# Reader_PN5108.net
KiCad netlist of a schematic drawn in Altium Designer
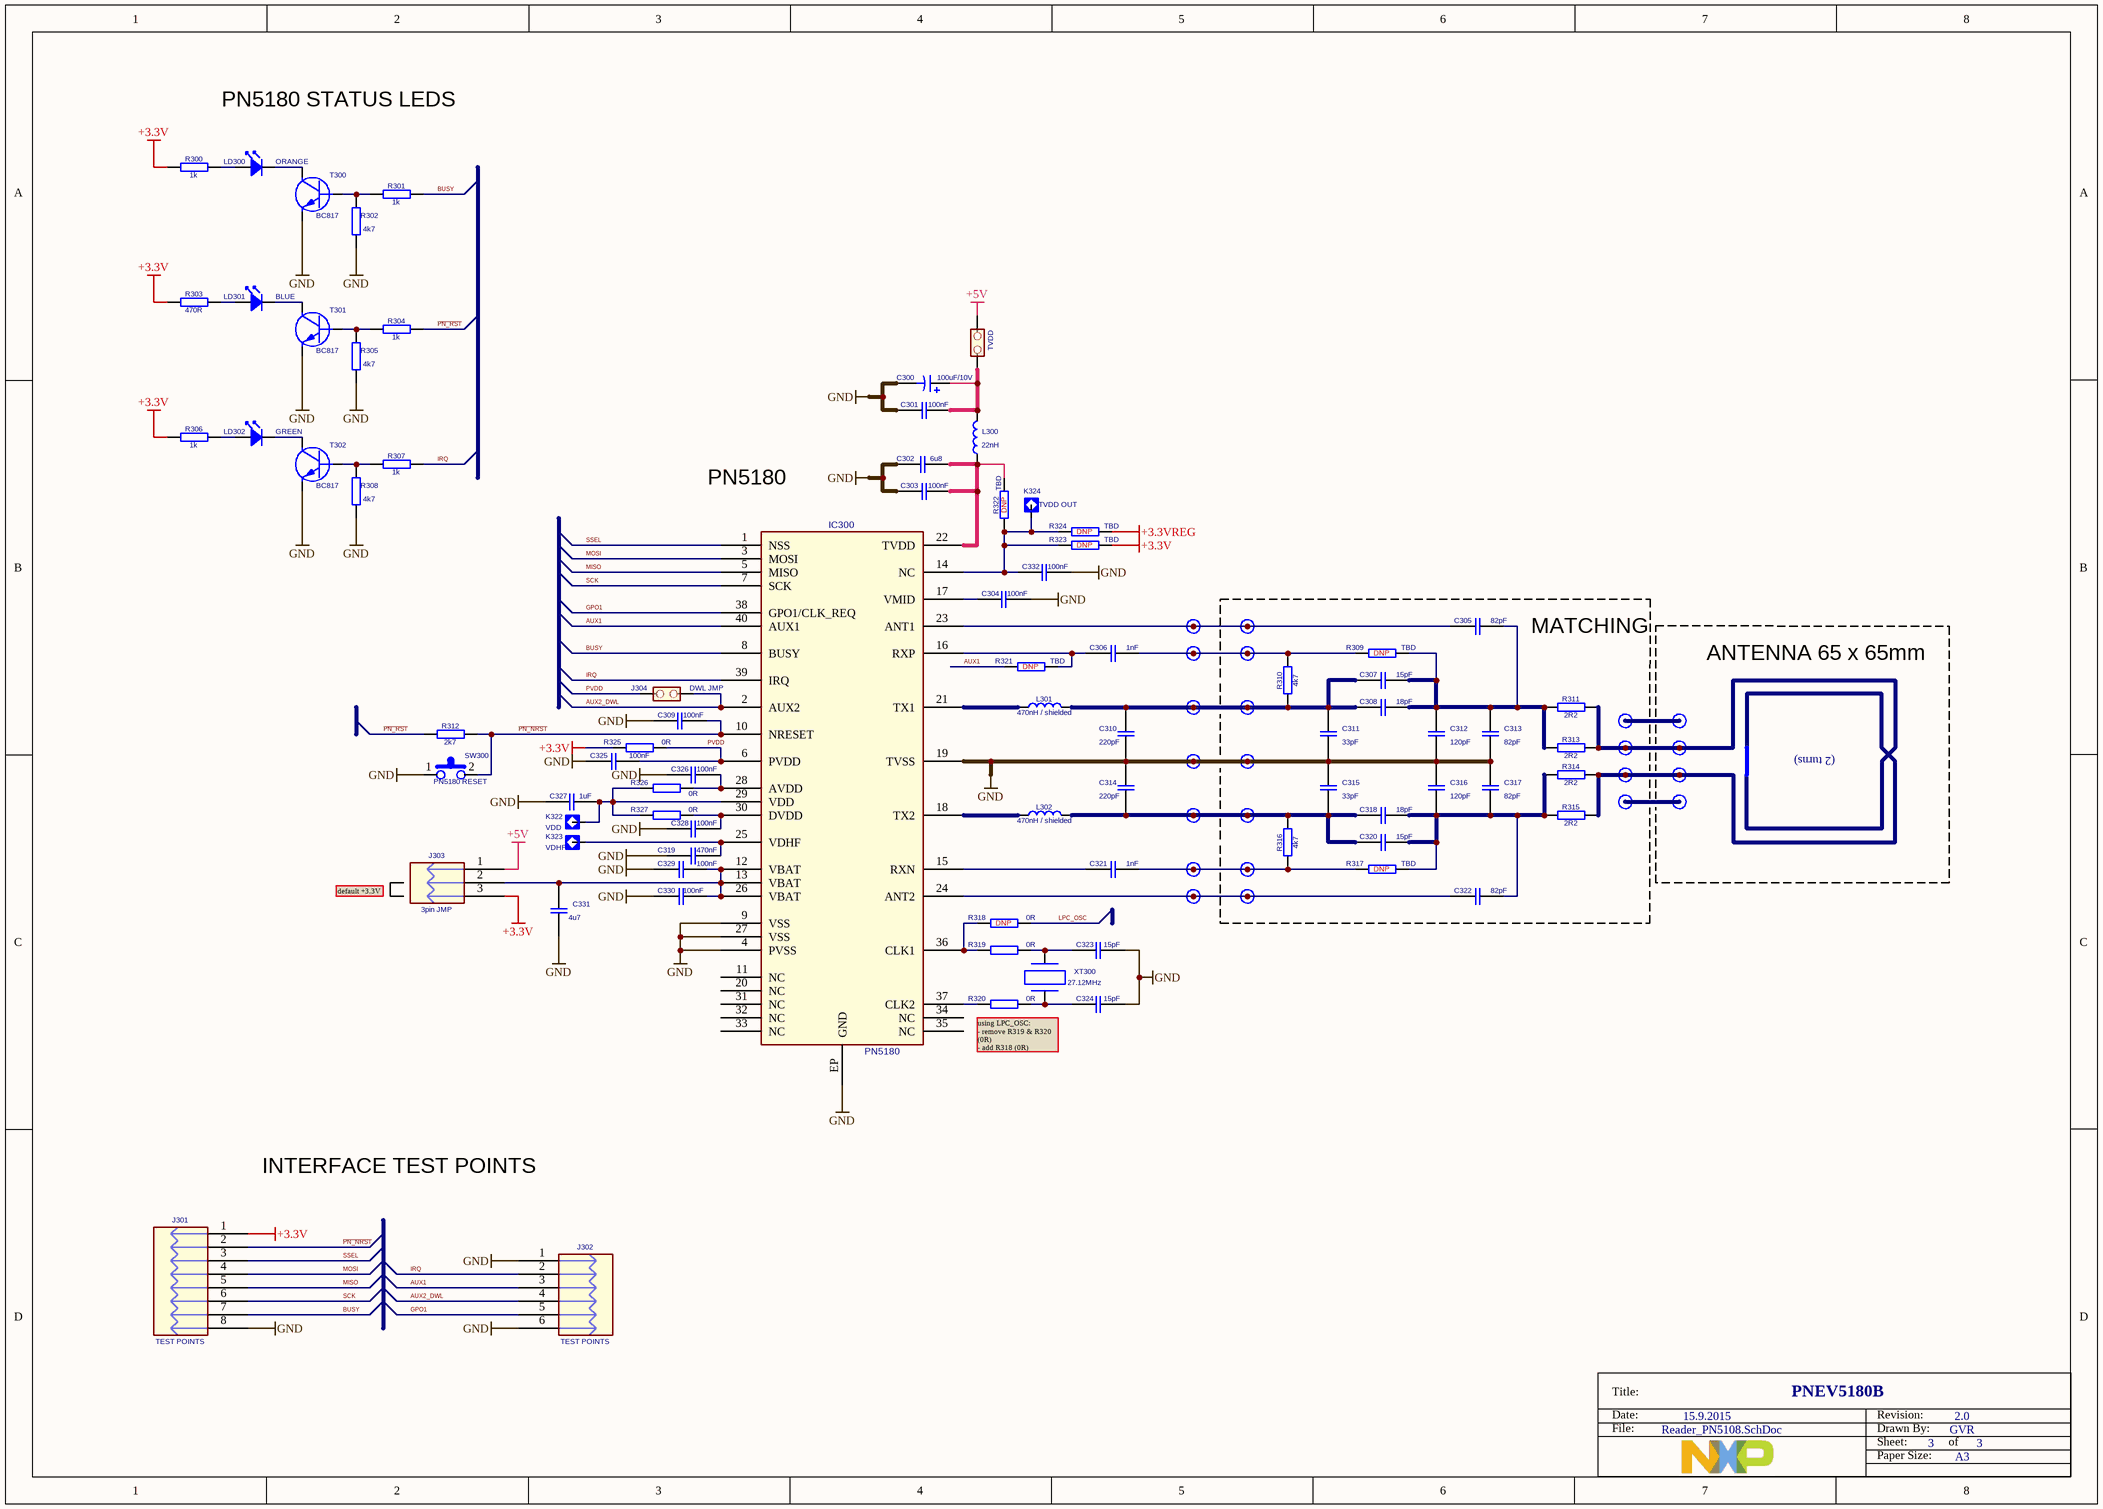
[diagram p0: Reader_PN5108.SchDoc]

(export (version "E")
  (design (tool "Eeschema 10.0.6"))
  (components
    (comp (ref "C300")
      (value "100uF/10V")
      (footprint "ALT_CP:C_TANTAL_B")
      (description "C_TANTAL_B")
      (libsource (lib "ALT_CP") (part "C_TANTAL_B"))
    )
    (comp (ref "C301")
      (value "100nF")
      (footprint "Y0603")
      (description "CAPC0603")
      (libsource (lib "ALT_CP") (part "CAPC0603"))
    )
    (comp (ref "C302")
      (value "6u8")
      (footprint "Y0603")
      (description "CAPC0603")
      (libsource (lib "ALT_CP") (part "CAPC0603"))
    )
    (comp (ref "C303")
      (value "100nF")
      (footprint "Y0603")
      (description "CAPC0603")
      (libsource (lib "ALT_CP") (part "CAPC0603"))
    )
    (comp (ref "C304")
      (value "100nF")
      (footprint "Y0603")
      (description "CAPC0603")
      (libsource (lib "ALT_CP") (part "CAPC0603"))
    )
    (comp (ref "C305")
      (value "82pF")
      (footprint "Y0805")
      (description "CAPC0805")
      (libsource (lib "ALT_CP") (part "CAPC0805"))
    )
    (comp (ref "C306")
      (value "1nF")
      (footprint "Y0805")
      (description "CAPC0805")
      (libsource (lib "ALT_CP") (part "CAPC0805"))
    )
    (comp (ref "C307")
      (value "15pF")
      (footprint "Y0805")
      (description "CAPC0805")
      (libsource (lib "ALT_CP") (part "CAPC0805"))
    )
    (comp (ref "C308")
      (value "18pF")
      (footprint "Y0805")
      (description "CAPC0805")
      (libsource (lib "ALT_CP") (part "CAPC0805"))
    )
    (comp (ref "C309")
      (value "100nF")
      (footprint "Y0603")
      (description "CAPC0603")
      (libsource (lib "ALT_CP") (part "CAPC0603"))
    )
    (comp (ref "C310")
      (value "220pF")
      (footprint "Y0805")
      (description "CAPC0805")
      (libsource (lib "ALT_CP") (part "CAPC0805"))
    )
    (comp (ref "C311")
      (value "33pF")
      (footprint "Y0805")
      (description "CAPC0805")
      (libsource (lib "ALT_CP") (part "CAPC0805"))
    )
    (comp (ref "C312")
      (value "120pF")
      (footprint "Y0805")
      (description "CAPC0805")
      (libsource (lib "ALT_CP") (part "CAPC0805"))
    )
    (comp (ref "C313")
      (value "82pF")
      (footprint "Y0805")
      (description "CAPC0805")
      (libsource (lib "ALT_CP") (part "CAPC0805"))
    )
    (comp (ref "C314")
      (value "220pF")
      (footprint "Y0805")
      (description "CAPC0805")
      (libsource (lib "ALT_CP") (part "CAPC0805"))
    )
    (comp (ref "C315")
      (value "33pF")
      (footprint "Y0805")
      (description "CAPC0805")
      (libsource (lib "ALT_CP") (part "CAPC0805"))
    )
    (comp (ref "C316")
      (value "120pF")
      (footprint "Y0805")
      (description "CAPC0805")
      (libsource (lib "ALT_CP") (part "CAPC0805"))
    )
    (comp (ref "C317")
      (value "82pF")
      (footprint "Y0805")
      (description "CAPC0805")
      (libsource (lib "ALT_CP") (part "CAPC0805"))
    )
    (comp (ref "C318")
      (value "18pF")
      (footprint "Y0805")
      (description "CAPC0805")
      (libsource (lib "ALT_CP") (part "CAPC0805"))
    )
    (comp (ref "C319")
      (value "470nF")
      (footprint "Y0603")
      (description "CAPC0603")
      (libsource (lib "ALT_CP") (part "CAPC0603"))
    )
    (comp (ref "C320")
      (value "15pF")
      (footprint "Y0805")
      (description "CAPC0805")
      (libsource (lib "ALT_CP") (part "CAPC0805"))
    )
    (comp (ref "C321")
      (value "1nF")
      (footprint "Y0805")
      (description "CAPC0805")
      (libsource (lib "ALT_CP") (part "CAPC0805"))
    )
    (comp (ref "C322")
      (value "82pF")
      (footprint "Y0805")
      (description "CAPC0805")
      (libsource (lib "ALT_CP") (part "CAPC0805"))
    )
    (comp (ref "C323")
      (value "15pF")
      (footprint "Y0603")
      (description "CAPC0603")
      (libsource (lib "ALT_CP") (part "CAPC0603"))
    )
    (comp (ref "C324")
      (value "15pF")
      (footprint "Y0603")
      (description "CAPC0603")
      (libsource (lib "ALT_CP") (part "CAPC0603"))
    )
    (comp (ref "C325")
      (value "100nF")
      (footprint "ALT_CP:Y0402")
      (description "CAPC0402")
      (libsource (lib "ALT_CP") (part "CAPC0402"))
    )
    (comp (ref "C326")
      (value "100nF")
      (footprint "Y0603")
      (description "CAPC0603")
      (libsource (lib "ALT_CP") (part "CAPC0603"))
    )
    (comp (ref "C327")
      (value "1uF")
      (footprint "Y0603")
      (description "CAPC0603")
      (libsource (lib "ALT_CP") (part "CAPC0603"))
    )
    (comp (ref "C328")
      (value "100nF")
      (footprint "Y0603")
      (description "CAPC0603")
      (libsource (lib "ALT_CP") (part "CAPC0603"))
    )
    (comp (ref "C329")
      (value "100nF")
      (footprint "ALT_CP:Y0402")
      (description "CAPC0402")
      (libsource (lib "ALT_CP") (part "CAPC0402"))
    )
    (comp (ref "C330")
      (value "100nF")
      (footprint "ALT_CP:Y0402")
      (description "CAPC0402")
      (libsource (lib "ALT_CP") (part "CAPC0402"))
    )
    (comp (ref "C331")
      (value "4u7")
      (footprint "Y0603")
      (description "CAPC0603")
      (libsource (lib "ALT_CP") (part "CAPC0603"))
    )
    (comp (ref "C332")
      (value "100nF")
      (footprint "Y0603")
      (description "CAPC0603")
      (libsource (lib "ALT_CP") (part "CAPC0603"))
    )
    (comp (ref "IC300")
      (value "PN5180")
      (footprint "ALT_CP:QFN50P600X600X100_HS-41N")
      (description "13.56 MHz Reader")
      (libsource (lib "ALT_CP") (part "PN5180"))
    )
    (comp (ref "J300")
      (value "TVDD")
      (footprint "CON2")
      (description "JMP2")
      (libsource (lib "") (part "JMP2_1"))
    )
    (comp (ref "J301")
      (value "TEST POINTS")
      (footprint "ALT_CP:CON8M-LINE")
      (description "CON8M_LINE")
      (libsource (lib "ALT_CP") (part "CON8M_LINE"))
    )
    (comp (ref "J302")
      (value "TEST POINTS")
      (footprint "ALT_CP:CON6M-LINE")
      (description "CON6M_LINE")
      (libsource (lib "ALT_CP") (part "CON6M_LINE"))
    )
    (comp (ref "J303")
      (value "3pin JMP")
      (footprint "ALT_CP:CON3M-LINE")
      (description "CON3M_LINE")
      (libsource (lib "ALT_CP") (part "CON3M_LINE"))
    )
    (comp (ref "J304")
      (value "DWL JMP")
      (footprint "CON2")
      (description "JMP2")
      (libsource (lib "ALT_CP") (part "JMP2"))
    )
    (comp (ref "K300")
      (value "TP_1.0mm")
      (footprint "CON1_PIN_Round_1.0x1.8mm")
      (libsource (lib "ALT_CP") (part "TP_1.0mm"))
    )
    (comp (ref "K301")
      (value "TP_1.0mm")
      (footprint "CON1_PIN_Round_1.0x1.8mm")
      (libsource (lib "ALT_CP") (part "TP_1.0mm"))
    )
    (comp (ref "K302")
      (value "TP_1.0mm")
      (footprint "CON1_PIN_Round_1.0x1.8mm")
      (libsource (lib "ALT_CP") (part "TP_1.0mm"))
    )
    (comp (ref "K303")
      (value "TP_1.0mm")
      (footprint "CON1_PIN_Round_1.0x1.8mm")
      (libsource (lib "ALT_CP") (part "TP_1.0mm"))
    )
    (comp (ref "K304")
      (value "TP_1.0mm")
      (footprint "CON1_PIN_Round_1.0x1.8mm")
      (libsource (lib "ALT_CP") (part "TP_1.0mm"))
    )
    (comp (ref "K305")
      (value "TP_1.0mm")
      (footprint "CON1_PIN_Round_1.0x1.8mm")
      (libsource (lib "ALT_CP") (part "TP_1.0mm"))
    )
    (comp (ref "K306")
      (value "TP_1.0mm")
      (footprint "CON1_PIN_Round_1.0x1.8mm")
      (libsource (lib "ALT_CP") (part "TP_1.0mm"))
    )
    (comp (ref "K307")
      (value "TP_1.0mm")
      (footprint "CON1_PIN_Round_1.0x1.8mm")
      (libsource (lib "ALT_CP") (part "TP_1.0mm"))
    )
    (comp (ref "K308")
      (value "TP_1.0mm")
      (footprint "CON1_PIN_Round_1.0x1.8mm")
      (libsource (lib "ALT_CP") (part "TP_1.0mm"))
    )
    (comp (ref "K309")
      (value "TP_1.0mm")
      (footprint "CON1_PIN_Round_1.0x1.8mm")
      (libsource (lib "ALT_CP") (part "TP_1.0mm"))
    )
    (comp (ref "K310")
      (value "TP_1.0mm")
      (footprint "CON1_PIN_Round_1.0x1.8mm")
      (libsource (lib "ALT_CP") (part "TP_1.0mm"))
    )
    (comp (ref "K311")
      (value "TP_1.0mm")
      (footprint "CON1_PIN_Round_1.0x1.8mm")
      (libsource (lib "ALT_CP") (part "TP_1.0mm"))
    )
    (comp (ref "K312")
      (value "TP_1.0mm")
      (footprint "CON1_PIN_Round_1.0x1.8mm")
      (libsource (lib "ALT_CP") (part "TP_1.0mm"))
    )
    (comp (ref "K313")
      (value "TP_1.0mm")
      (footprint "CON1_PIN_Round_1.0x1.8mm")
      (libsource (lib "ALT_CP") (part "TP_1.0mm"))
    )
    (comp (ref "K314")
      (value "TP_1.0mm")
      (footprint "CON1_PIN_Round_1.0x1.8mm")
      (libsource (lib "ALT_CP") (part "TP_1.0mm"))
    )
    (comp (ref "K315")
      (value "TP_1.0mm")
      (footprint "CON1_PIN_Round_1.0x1.8mm")
      (libsource (lib "ALT_CP") (part "TP_1.0mm"))
    )
    (comp (ref "K316")
      (value "TP_1.0mm")
      (footprint "CON1_PIN_Round_1.0x1.8mm")
      (libsource (lib "ALT_CP") (part "TP_1.0mm"))
    )
    (comp (ref "K317")
      (value "TP_1.0mm")
      (footprint "CON1_PIN_Round_1.0x1.8mm")
      (libsource (lib "ALT_CP") (part "TP_1.0mm"))
    )
    (comp (ref "K318")
      (value "TP_1.0mm")
      (footprint "CON1_PIN_Round_1.0x1.8mm")
      (libsource (lib "ALT_CP") (part "TP_1.0mm"))
    )
    (comp (ref "K319")
      (value "TP_1.0mm")
      (footprint "CON1_PIN_Round_1.0x1.8mm")
      (libsource (lib "ALT_CP") (part "TP_1.0mm"))
    )
    (comp (ref "K320")
      (value "TP_1.0mm")
      (footprint "CON1_PIN_Round_1.0x1.8mm")
      (libsource (lib "ALT_CP") (part "TP_1.0mm"))
    )
    (comp (ref "K321")
      (value "TP_1.0mm")
      (footprint "CON1_PIN_Round_1.0x1.8mm")
      (libsource (lib "ALT_CP") (part "TP_1.0mm"))
    )
    (comp (ref "K322")
      (value "VDD")
      (footprint "ALT_CP:TESTP_ROUND_1.0mm")
      (description "TP1")
      (libsource (lib "ALT_CP") (part "TP1"))
    )
    (comp (ref "K323")
      (value "VDHF")
      (footprint "ALT_CP:TESTP_ROUND_1.0mm")
      (description "TP1")
      (libsource (lib "ALT_CP") (part "TP1"))
    )
    (comp (ref "K324")
      (value "TVDD OUT")
      (footprint "ALT_CP:TESTP_ROUND_1.0mm")
      (description "TP1")
      (libsource (lib "ALT_CP") (part "TP1"))
    )
    (comp (ref "L300")
      (value "22nH")
      (footprint "Y0805")
      (description "INDC0805")
      (libsource (lib "ALT_CP") (part "INDC0805"))
    )
    (comp (ref "L301")
      (value "470nH / shielded")
      (footprint "ALT_CP:INDCC_1812_1210")
      (description "INDC1812")
      (fields (field (name "Comment") "470nH / shielded (1210)"))
      (libsource (lib "ALT_CP") (part "INDC1812"))
    )
    (comp (ref "L302")
      (value "470nH / shielded")
      (footprint "ALT_CP:INDCC_1812_1210")
      (description "INDC1812")
      (fields (field (name "Comment") "470nH / shielded (1210)"))
      (libsource (lib "ALT_CP") (part "INDC1812"))
    )
    (comp (ref "LD300")
      (value "ORANGE")
      (footprint "ALT_CP:LED_0603")
      (description "LEDY0603")
      (libsource (lib "ALT_CP") (part "LEDY0603"))
    )
    (comp (ref "LD301")
      (value "BLUE")
      (footprint "ALT_CP:LED_0603")
      (description "LEDY0603")
      (libsource (lib "ALT_CP") (part "LEDY0603"))
    )
    (comp (ref "LD302")
      (value "GREEN")
      (footprint "ALT_CP:LED_0603")
      (description "LEDY0603")
      (libsource (lib "ALT_CP") (part "LEDY0603"))
    )
    (comp (ref "NT1")
      (value "Net_Tie")
      (footprint "ALT_CP:Net_Tie_SMT_0.406mm")
      (description "Component for shorting nets in design")
      (libsource (lib "ALT_CP") (part "Net_Tie"))
    )
    (comp (ref "R300")
      (value "1k")
      (footprint "Y0603")
      (description "RESC0603")
      (libsource (lib "ALT_CP") (part "RESC0603"))
    )
    (comp (ref "R301")
      (value "1k")
      (footprint "Y0603")
      (description "RESC0603")
      (libsource (lib "ALT_CP") (part "RESC0603"))
    )
    (comp (ref "R302")
      (value "4k7")
      (footprint "Y0603")
      (description "RESC0603")
      (libsource (lib "ALT_CP") (part "RESC0603"))
    )
    (comp (ref "R303")
      (value "470R")
      (footprint "Y0603")
      (description "RESC0603")
      (libsource (lib "ALT_CP") (part "RESC0603"))
    )
    (comp (ref "R304")
      (value "1k")
      (footprint "Y0603")
      (description "RESC0603")
      (libsource (lib "ALT_CP") (part "RESC0603"))
    )
    (comp (ref "R305")
      (value "4k7")
      (footprint "Y0603")
      (description "RESC0603")
      (libsource (lib "ALT_CP") (part "RESC0603"))
    )
    (comp (ref "R306")
      (value "1k")
      (footprint "Y0603")
      (description "RESC0603")
      (libsource (lib "ALT_CP") (part "RESC0603"))
    )
    (comp (ref "R307")
      (value "1k")
      (footprint "Y0603")
      (description "RESC0603")
      (libsource (lib "ALT_CP") (part "RESC0603"))
    )
    (comp (ref "R308")
      (value "4k7")
      (footprint "Y0603")
      (description "RESC0603")
      (libsource (lib "ALT_CP") (part "RESC0603"))
    )
    (comp (ref "R309")
      (value "TBD")
      (footprint "Y0805")
      (description "RESC0805")
      (fields (field (name "DNP") "DNP") (field (name "Comment") "TBD DNP"))
      (libsource (lib "ALT_CP") (part "RESC0805"))
    )
    (comp (ref "R310")
      (value "4k7")
      (footprint "Y0805")
      (description "RESC0805")
      (libsource (lib "ALT_CP") (part "RESC0805"))
    )
    (comp (ref "R311")
      (value "2R2")
      (footprint "Y0805")
      (description "RESC0805")
      (libsource (lib "ALT_CP") (part "RESC0805"))
    )
    (comp (ref "R312")
      (value "2k7")
      (footprint "Y0603")
      (description "RESC0603")
      (libsource (lib "ALT_CP") (part "RESC0603"))
    )
    (comp (ref "R313")
      (value "2R2")
      (footprint "Y0805")
      (description "RESC0805")
      (libsource (lib "ALT_CP") (part "RESC0805"))
    )
    (comp (ref "R314")
      (value "2R2")
      (footprint "Y0805")
      (description "RESC0805")
      (libsource (lib "ALT_CP") (part "RESC0805"))
    )
    (comp (ref "R315")
      (value "2R2")
      (footprint "Y0805")
      (description "RESC0805")
      (libsource (lib "ALT_CP") (part "RESC0805"))
    )
    (comp (ref "R316")
      (value "4k7")
      (footprint "Y0805")
      (description "RESC0805")
      (libsource (lib "ALT_CP") (part "RESC0805"))
    )
    (comp (ref "R317")
      (value "TBD")
      (footprint "Y0805")
      (description "RESC0805")
      (fields (field (name "DNP") "DNP") (field (name "Comment") "TBD DNP"))
      (libsource (lib "ALT_CP") (part "RESC0805"))
    )
    (comp (ref "R318")
      (value "0R")
      (footprint "Y0603")
      (description "RESC0603")
      (fields (field (name "DNP") "DNP") (field (name "Comment") "0R DNP"))
      (libsource (lib "ALT_CP") (part "RESC0603"))
    )
    (comp (ref "R319")
      (value "0R")
      (footprint "Y0603")
      (description "RESC0603")
      (libsource (lib "ALT_CP") (part "RESC0603"))
    )
    (comp (ref "R320")
      (value "0R")
      (footprint "Y0603")
      (description "RESC0603")
      (libsource (lib "ALT_CP") (part "RESC0603"))
    )
    (comp (ref "R321")
      (value "TBD")
      (footprint "Y0603")
      (description "RESC0603")
      (fields (field (name "DNP") "DNP") (field (name "Comment") "TBD DNP"))
      (libsource (lib "ALT_CP") (part "RESC0603"))
    )
    (comp (ref "R322")
      (value "TBD")
      (footprint "Y0603")
      (description "RESC0603")
      (fields (field (name "DNP") "DNP") (field (name "Comment") "TBD DNP"))
      (libsource (lib "ALT_CP") (part "RESC0603"))
    )
    (comp (ref "R323")
      (value "TBD")
      (footprint "Y0603")
      (description "RESC0603")
      (fields (field (name "DNP") "DNP") (field (name "Comment") "TBD DNP"))
      (libsource (lib "ALT_CP") (part "RESC0603"))
    )
    (comp (ref "R324")
      (value "TBD")
      (footprint "Y0603")
      (description "RESC0603")
      (fields (field (name "DNP") "DNP") (field (name "Comment") "TBD DNP"))
      (libsource (lib "ALT_CP") (part "RESC0603"))
    )
    (comp (ref "R325")
      (value "0R")
      (footprint "Y0603")
      (description "RESC0603")
      (libsource (lib "ALT_CP") (part "RESC0603"))
    )
    (comp (ref "R326")
      (value "0R")
      (footprint "Y0603")
      (description "RESC0603")
      (libsource (lib "ALT_CP") (part "RESC0603"))
    )
    (comp (ref "R327")
      (value "0R")
      (footprint "Y0603")
      (description "RESC0603")
      (libsource (lib "ALT_CP") (part "RESC0603"))
    )
    (comp (ref "SW300")
      (value "DTSM-32S-B")
      (footprint "ALT_CP:SW_DTSM-32S-B")
      (fields (field (name "ALTIUM_UNNAMED_1") "PN5180 RESET"))
      (libsource (lib "ALT_CP") (part "SWITCH_SMD"))
    )
    (comp (ref "T300") (value "BC817") (footprint "SOT-23") (libsource (lib "ALT_CP") (part "BC817")))
    (comp (ref "T301") (value "BC817") (footprint "SOT-23") (libsource (lib "ALT_CP") (part "BC817")))
    (comp (ref "T302") (value "BC817") (footprint "SOT-23") (libsource (lib "ALT_CP") (part "BC817")))
    (comp (ref "XT300")
      (value "27.12MHz")
      (footprint "QUARTZ_32SMX")
      (description "QUARTZ_32SMX")
      (libsource (lib "ALT_CP") (part "QUARTZ_32SMX"))
    )
  )
  (nets
    (net (code "1") (name "+3.3V") (class "Default")
      (node (ref "J301") (pin "1") (pinfunction "P1_1") (pintype "passive"))
      (node (ref "J303") (pin "3") (pinfunction "P3_3") (pintype "passive"))
      (node (ref "R300") (pin "2") (pintype "passive"))
      (node (ref "R303") (pin "2") (pintype "passive"))
      (node (ref "R306") (pin "2") (pintype "passive"))
      (node (ref "R323") (pin "1") (pintype "passive"))
      (node (ref "R325") (pin "2") (pintype "passive"))
    )
    (net (code "2") (name "+3.3VREG") (class "Default") (node (ref "R324") (pin "1") (pintype "passive")))
    (net (code "3") (name "+5V") (class "Default")
      (node (ref "J300") (pin "2") (pinfunction "2_2") (pintype "passive"))
      (node (ref "J303") (pin "1") (pinfunction "P1_1") (pintype "passive"))
    )
    (net (code "4") (name "/AUX1") (class "Default")
      (node (ref "IC300") (pin "40") (pinfunction "AUX1_40") (pintype "passive"))
      (node (ref "J302") (pin "3") (pinfunction "P3_3") (pintype "passive"))
      (node (ref "R321") (pin "2") (pintype "passive"))
    )
    (net (code "5") (name "/AUX2_DWL") (class "Default")
      (node (ref "IC300") (pin "2") (pinfunction "AUX2_2") (pintype "passive"))
      (node (ref "J302") (pin "4") (pinfunction "P4_4") (pintype "passive"))
      (node (ref "J304") (pin "2") (pinfunction "2_2") (pintype "passive"))
    )
    (net (code "6") (name "/BUSY") (class "Default")
      (node (ref "IC300") (pin "8") (pinfunction "BUSY_8") (pintype "passive"))
      (node (ref "J301") (pin "7") (pinfunction "P7_7") (pintype "passive"))
      (node (ref "R301") (pin "2") (pintype "passive"))
    )
    (net (code "7") (name "/GPO1") (class "Default")
      (node (ref "IC300") (pin "38") (pinfunction "GPO1/CLK_REQ_38") (pintype "passive"))
      (node (ref "J302") (pin "5") (pinfunction "P5_5") (pintype "passive"))
    )
    (net (code "8") (name "/IRQ") (class "Default")
      (node (ref "IC300") (pin "39") (pinfunction "IRQ_39") (pintype "passive"))
      (node (ref "J302") (pin "2") (pinfunction "P2_2") (pintype "passive"))
      (node (ref "R307") (pin "2") (pintype "passive"))
    )
    (net (code "9") (name "/LPC_OSC") (class "Default") (node (ref "R318") (pin "1") (pintype "passive")))
    (net (code "10") (name "/MISO") (class "Default")
      (node (ref "IC300") (pin "5") (pinfunction "MISO_5") (pintype "passive"))
      (node (ref "J301") (pin "5") (pinfunction "P5_5") (pintype "passive"))
    )
    (net (code "11") (name "/MOSI") (class "Default")
      (node (ref "IC300") (pin "3") (pinfunction "MOSI_3") (pintype "passive"))
      (node (ref "J301") (pin "4") (pinfunction "P4_4") (pintype "passive"))
    )
    (net (code "12") (name "/PVDD") (class "Default")
      (node (ref "C325") (pin "2") (pintype "passive"))
      (node (ref "IC300") (pin "6") (pinfunction "PVDD_6") (pintype "passive"))
      (node (ref "J304") (pin "1") (pinfunction "1_1") (pintype "passive"))
      (node (ref "R325") (pin "1") (pintype "passive"))
    )
    (net (code "13") (name "/SCK") (class "Default")
      (node (ref "IC300") (pin "7") (pinfunction "SCK_7") (pintype "passive"))
      (node (ref "J301") (pin "6") (pinfunction "P6_6") (pintype "passive"))
    )
    (net (code "14") (name "/SSEL") (class "Default")
      (node (ref "IC300") (pin "1") (pinfunction "NSS_1") (pintype "passive"))
      (node (ref "J301") (pin "3") (pinfunction "P3_3") (pintype "passive"))
    )
    (net (code "15") (name "/~{PN_NRST}") (class "Default")
      (node (ref "C309") (pin "1") (pintype "passive"))
      (node (ref "IC300") (pin "10") (pinfunction "NRESET_10") (pintype "passive"))
      (node (ref "J301") (pin "2") (pinfunction "P2_2") (pintype "passive"))
      (node (ref "R312") (pin "2") (pintype "passive"))
      (node (ref "SW300") (pin "2") (pinfunction "2_2") (pintype "passive"))
    )
    (net (code "16") (name "/~{PN_RST}") (class "Default")
      (node (ref "R304") (pin "2") (pintype "passive"))
      (node (ref "R312") (pin "1") (pintype "passive"))
    )
    (net (code "17") (name "GND") (class "Default")
      (node (ref "C300") (pin "2") (pinfunction "2_2") (pintype "passive"))
      (node (ref "C301") (pin "1") (pintype "passive"))
      (node (ref "C302") (pin "2") (pintype "passive"))
      (node (ref "C303") (pin "1") (pintype "passive"))
      (node (ref "C304") (pin "1") (pintype "passive"))
      (node (ref "C309") (pin "2") (pintype "passive"))
      (node (ref "C310") (pin "1") (pintype "passive"))
      (node (ref "C311") (pin "1") (pintype "passive"))
      (node (ref "C312") (pin "1") (pintype "passive"))
      (node (ref "C313") (pin "1") (pintype "passive"))
      (node (ref "C314") (pin "2") (pintype "passive"))
      (node (ref "C315") (pin "2") (pintype "passive"))
      (node (ref "C316") (pin "2") (pintype "passive"))
      (node (ref "C317") (pin "2") (pintype "passive"))
      (node (ref "C319") (pin "2") (pintype "passive"))
      (node (ref "C323") (pin "1") (pintype "passive"))
      (node (ref "C324") (pin "1") (pintype "passive"))
      (node (ref "C325") (pin "1") (pintype "passive"))
      (node (ref "C326") (pin "2") (pintype "passive"))
      (node (ref "C327") (pin "2") (pintype "passive"))
      (node (ref "C328") (pin "2") (pintype "passive"))
      (node (ref "C329") (pin "1") (pintype "passive"))
      (node (ref "C330") (pin "1") (pintype "passive"))
      (node (ref "C331") (pin "2") (pintype "passive"))
      (node (ref "C332") (pin "1") (pintype "passive"))
      (node (ref "IC300") (pin "19") (pinfunction "TVSS_19") (pintype "passive"))
      (node (ref "IC300") (pin "27") (pinfunction "VSS_27") (pintype "passive"))
      (node (ref "IC300") (pin "4") (pinfunction "PVSS_4") (pintype "passive"))
      (node (ref "IC300") (pin "9") (pinfunction "VSS_9") (pintype "passive"))
      (node (ref "IC300") (pin "EP") (pinfunction "GND_EP") (pintype "passive"))
      (node (ref "J301") (pin "8") (pinfunction "P8_8") (pintype "passive"))
      (node (ref "J302") (pin "1") (pinfunction "P1_1") (pintype "passive"))
      (node (ref "J302") (pin "6") (pinfunction "P6_6") (pintype "passive"))
      (node (ref "K310") (pin "1") (pintype "passive"))
      (node (ref "K311") (pin "1") (pintype "passive"))
      (node (ref "R302") (pin "2") (pintype "passive"))
      (node (ref "R305") (pin "2") (pintype "passive"))
      (node (ref "R308") (pin "2") (pintype "passive"))
      (node (ref "SW300") (pin "1") (pinfunction "1_1") (pintype "passive"))
      (node (ref "T300") (pin "2") (pinfunction "E_2") (pintype "passive"))
      (node (ref "T301") (pin "2") (pinfunction "E_2") (pintype "passive"))
      (node (ref "T302") (pin "2") (pinfunction "E_2") (pintype "passive"))
    )
    (net (code "18") (name "Net-(C300-Pad1)") (class "Default")
      (node (ref "C300") (pin "1") (pinfunction "1_1") (pintype "passive"))
      (node (ref "C301") (pin "2") (pintype "passive"))
      (node (ref "J300") (pin "1") (pinfunction "1_1") (pintype "passive"))
      (node (ref "L300") (pin "2") (pintype "passive"))
    )
    (net (code "19") (name "Net-(C305-Pad2)") (class "Default")
      (node (ref "C305") (pin "2") (pintype "passive"))
      (node (ref "C307") (pin "2") (pintype "passive"))
      (node (ref "C308") (pin "2") (pintype "passive"))
      (node (ref "C312") (pin "2") (pintype "passive"))
      (node (ref "C313") (pin "2") (pintype "passive"))
      (node (ref "R309") (pin "1") (pintype "passive"))
      (node (ref "R311") (pin "2") (pintype "passive"))
      (node (ref "R313") (pin "2") (pintype "passive"))
    )
    (net (code "20") (name "Net-(C306-Pad2)") (class "Default")
      (node (ref "C306") (pin "2") (pintype "passive"))
      (node (ref "K302") (pin "1") (pintype "passive"))
      (node (ref "K303") (pin "1") (pintype "passive"))
      (node (ref "R309") (pin "2") (pintype "passive"))
      (node (ref "R310") (pin "1") (pintype "passive"))
    )
    (net (code "21") (name "Net-(C307-Pad1)") (class "Default")
      (node (ref "C307") (pin "1") (pintype "passive"))
      (node (ref "C308") (pin "1") (pintype "passive"))
      (node (ref "C310") (pin "2") (pintype "passive"))
      (node (ref "C311") (pin "2") (pintype "passive"))
      (node (ref "K304") (pin "1") (pintype "passive"))
      (node (ref "K305") (pin "1") (pintype "passive"))
      (node (ref "L301") (pin "2") (pintype "passive"))
      (node (ref "R310") (pin "2") (pintype "passive"))
    )
    (net (code "22") (name "Net-(C314-Pad1)") (class "Default")
      (node (ref "C314") (pin "1") (pintype "passive"))
      (node (ref "C315") (pin "1") (pintype "passive"))
      (node (ref "C318") (pin "1") (pintype "passive"))
      (node (ref "C320") (pin "1") (pintype "passive"))
      (node (ref "K316") (pin "1") (pintype "passive"))
      (node (ref "K317") (pin "1") (pintype "passive"))
      (node (ref "L302") (pin "2") (pintype "passive"))
      (node (ref "R316") (pin "1") (pintype "passive"))
    )
    (net (code "23") (name "Net-(C316-Pad1)") (class "Default")
      (node (ref "C316") (pin "1") (pintype "passive"))
      (node (ref "C317") (pin "1") (pintype "passive"))
      (node (ref "C318") (pin "2") (pintype "passive"))
      (node (ref "C320") (pin "2") (pintype "passive"))
      (node (ref "C322") (pin "2") (pintype "passive"))
      (node (ref "R314") (pin "2") (pintype "passive"))
      (node (ref "R315") (pin "2") (pintype "passive"))
      (node (ref "R317") (pin "1") (pintype "passive"))
    )
    (net (code "24") (name "Net-(C321-Pad2)") (class "Default")
      (node (ref "C321") (pin "2") (pintype "passive"))
      (node (ref "K318") (pin "1") (pintype "passive"))
      (node (ref "K319") (pin "1") (pintype "passive"))
      (node (ref "R316") (pin "2") (pintype "passive"))
      (node (ref "R317") (pin "2") (pintype "passive"))
    )
    (net (code "25") (name "Net-(C324-Pad2)") (class "Default")
      (node (ref "C324") (pin "2") (pintype "passive"))
      (node (ref "R320") (pin "1") (pintype "passive"))
      (node (ref "XT300") (pin "1") (pinfunction "1_1") (pintype "passive"))
    )
    (net (code "26") (name "Net-(C332-Pad2)") (class "Default")
      (node (ref "C332") (pin "2") (pintype "passive"))
      (node (ref "IC300") (pin "14") (pinfunction "NC_14") (pintype "passive"))
      (node (ref "K324") (pin "1") (pintype "passive"))
      (node (ref "R322") (pin "2") (pintype "passive"))
      (node (ref "R323") (pin "2") (pintype "passive"))
      (node (ref "R324") (pin "2") (pintype "passive"))
    )
    (net (code "27") (name "Net-(IC300-ANT1)") (class "Default")
      (node (ref "C305") (pin "1") (pintype "passive"))
      (node (ref "IC300") (pin "23") (pinfunction "ANT1_23") (pintype "passive"))
      (node (ref "K300") (pin "1") (pintype "passive"))
      (node (ref "K301") (pin "1") (pintype "passive"))
    )
    (net (code "28") (name "Net-(IC300-ANT2)") (class "Default")
      (node (ref "C322") (pin "1") (pintype "passive"))
      (node (ref "IC300") (pin "24") (pinfunction "ANT2_24") (pintype "passive"))
      (node (ref "K320") (pin "1") (pintype "passive"))
      (node (ref "K321") (pin "1") (pintype "passive"))
    )
    (net (code "29") (name "Net-(IC300-AVDD)") (class "Default")
      (node (ref "C326") (pin "1") (pintype "passive"))
      (node (ref "IC300") (pin "28") (pinfunction "AVDD_28") (pintype "passive"))
      (node (ref "R326") (pin "1") (pintype "passive"))
    )
    (net (code "30") (name "Net-(IC300-CLK1)") (class "Default")
      (node (ref "IC300") (pin "36") (pinfunction "CLK1_36") (pintype "passive"))
      (node (ref "R318") (pin "2") (pintype "passive"))
      (node (ref "R319") (pin "2") (pintype "passive"))
    )
    (net (code "31") (name "Net-(IC300-CLK2)") (class "Default")
      (node (ref "IC300") (pin "37") (pinfunction "CLK2_37") (pintype "passive"))
      (node (ref "R320") (pin "2") (pintype "passive"))
    )
    (net (code "32") (name "Net-(IC300-DVDD)") (class "Default")
      (node (ref "C328") (pin "1") (pintype "passive"))
      (node (ref "IC300") (pin "30") (pinfunction "DVDD_30") (pintype "passive"))
      (node (ref "R327") (pin "1") (pintype "passive"))
    )
    (net (code "33") (name "Net-(IC300-RXN)") (class "Default")
      (node (ref "C321") (pin "1") (pintype "passive"))
      (node (ref "IC300") (pin "15") (pinfunction "RXN_15") (pintype "passive"))
    )
    (net (code "34") (name "Net-(IC300-RXP)") (class "Default")
      (node (ref "C306") (pin "1") (pintype "passive"))
      (node (ref "IC300") (pin "16") (pinfunction "RXP_16") (pintype "passive"))
      (node (ref "R321") (pin "1") (pintype "passive"))
    )
    (net (code "35") (name "Net-(IC300-TVDD)") (class "Default")
      (node (ref "C302") (pin "1") (pintype "passive"))
      (node (ref "C303") (pin "2") (pintype "passive"))
      (node (ref "IC300") (pin "22") (pinfunction "TVDD_22") (pintype "passive"))
      (node (ref "L300") (pin "1") (pintype "passive"))
      (node (ref "R322") (pin "1") (pintype "passive"))
    )
    (net (code "36") (name "Net-(IC300-TX1)") (class "Default")
      (node (ref "IC300") (pin "21") (pinfunction "TX1_21") (pintype "passive"))
      (node (ref "L301") (pin "1") (pintype "passive"))
    )
    (net (code "37") (name "Net-(IC300-TX2)") (class "Default")
      (node (ref "IC300") (pin "18") (pinfunction "TX2_18") (pintype "passive"))
      (node (ref "L302") (pin "1") (pintype "passive"))
    )
    (net (code "38") (name "Net-(IC300-VDD)") (class "Default")
      (node (ref "C327") (pin "1") (pintype "passive"))
      (node (ref "IC300") (pin "29") (pinfunction "VDD_29") (pintype "passive"))
      (node (ref "K322") (pin "1") (pintype "passive"))
      (node (ref "R326") (pin "2") (pintype "passive"))
      (node (ref "R327") (pin "2") (pintype "passive"))
    )
    (net (code "39") (name "Net-(IC300-VDHF)") (class "Default")
      (node (ref "C319") (pin "1") (pintype "passive"))
      (node (ref "IC300") (pin "25") (pinfunction "VDHF_25") (pintype "passive"))
      (node (ref "K323") (pin "1") (pintype "passive"))
    )
    (net (code "40") (name "Net-(IC300-VMID)") (class "Default")
      (node (ref "C304") (pin "2") (pintype "passive"))
      (node (ref "IC300") (pin "17") (pinfunction "VMID_17") (pintype "passive"))
    )
    (net (code "41") (name "Net-(J303-P2)") (class "Default")
      (node (ref "C329") (pin "2") (pintype "passive"))
      (node (ref "C330") (pin "2") (pintype "passive"))
      (node (ref "C331") (pin "1") (pintype "passive"))
      (node (ref "IC300") (pin "12") (pinfunction "VBAT_12") (pintype "passive"))
      (node (ref "IC300") (pin "13") (pinfunction "VBAT_13") (pintype "passive"))
      (node (ref "IC300") (pin "26") (pinfunction "VBAT_26") (pintype "passive"))
      (node (ref "J303") (pin "2") (pinfunction "P2_2") (pintype "passive"))
    )
    (net (code "42") (name "Net-(K306-Pad1)") (class "Default")
      (node (ref "K306") (pin "1") (pintype "passive"))
      (node (ref "K307") (pin "1") (pintype "passive"))
    )
    (net (code "43") (name "Net-(K308-Pad1)") (class "Default")
      (node (ref "K308") (pin "1") (pintype "passive"))
      (node (ref "K309") (pin "1") (pintype "passive"))
      (node (ref "NT1") (pin "1") (pintype "passive"))
      (node (ref "R311") (pin "1") (pintype "passive"))
      (node (ref "R313") (pin "1") (pintype "passive"))
    )
    (net (code "44") (name "Net-(K312-Pad1)") (class "Default")
      (node (ref "K312") (pin "1") (pintype "passive"))
      (node (ref "K313") (pin "1") (pintype "passive"))
      (node (ref "NT1") (pin "2") (pintype "passive"))
      (node (ref "R314") (pin "1") (pintype "passive"))
      (node (ref "R315") (pin "1") (pintype "passive"))
    )
    (net (code "45") (name "Net-(K314-Pad1)") (class "Default")
      (node (ref "K314") (pin "1") (pintype "passive"))
      (node (ref "K315") (pin "1") (pintype "passive"))
    )
    (net (code "46") (name "Net-(LD300-Pad2)") (class "Default")
      (node (ref "LD300") (pin "2") (pintype "passive"))
      (node (ref "R300") (pin "1") (pintype "passive"))
    )
    (net (code "47") (name "Net-(LD301-Pad2)") (class "Default")
      (node (ref "LD301") (pin "2") (pintype "passive"))
      (node (ref "R303") (pin "1") (pintype "passive"))
    )
    (net (code "48") (name "Net-(LD302-Pad2)") (class "Default")
      (node (ref "LD302") (pin "2") (pintype "passive"))
      (node (ref "R306") (pin "1") (pintype "passive"))
    )
    (net (code "49") (name "Net-(T300-B)") (class "Default")
      (node (ref "R301") (pin "1") (pintype "passive"))
      (node (ref "R302") (pin "1") (pintype "passive"))
      (node (ref "T300") (pin "1") (pinfunction "B_1") (pintype "passive"))
    )
    (net (code "50") (name "Net-(T300-C)") (class "Default")
      (node (ref "LD300") (pin "1") (pintype "passive"))
      (node (ref "T300") (pin "3") (pinfunction "C_3") (pintype "passive"))
    )
    (net (code "51") (name "Net-(T301-B)") (class "Default")
      (node (ref "R304") (pin "1") (pintype "passive"))
      (node (ref "R305") (pin "1") (pintype "passive"))
      (node (ref "T301") (pin "1") (pinfunction "B_1") (pintype "passive"))
    )
    (net (code "52") (name "Net-(T301-C)") (class "Default")
      (node (ref "LD301") (pin "1") (pintype "passive"))
      (node (ref "T301") (pin "3") (pinfunction "C_3") (pintype "passive"))
    )
    (net (code "53") (name "Net-(T302-B)") (class "Default")
      (node (ref "R307") (pin "1") (pintype "passive"))
      (node (ref "R308") (pin "1") (pintype "passive"))
      (node (ref "T302") (pin "1") (pinfunction "B_1") (pintype "passive"))
    )
    (net (code "54") (name "Net-(T302-C)") (class "Default")
      (node (ref "LD302") (pin "1") (pintype "passive"))
      (node (ref "T302") (pin "3") (pinfunction "C_3") (pintype "passive"))
    )
    (net (code "55") (name "Net-(XT300-2)") (class "Default")
      (node (ref "C323") (pin "2") (pintype "passive"))
      (node (ref "R319") (pin "1") (pintype "passive"))
      (node (ref "XT300") (pin "3") (pinfunction "2_3") (pintype "passive"))
    )
    (net (code "56") (name "unconnected-(IC300-NC-Pad11)") (class "Default")
      (node (ref "IC300") (pin "11") (pinfunction "NC_11") (pintype "passive"))
    )
    (net (code "57") (name "unconnected-(IC300-NC-Pad20)") (class "Default")
      (node (ref "IC300") (pin "20") (pinfunction "NC_20") (pintype "passive"))
    )
    (net (code "58") (name "unconnected-(IC300-NC-Pad31)") (class "Default")
      (node (ref "IC300") (pin "31") (pinfunction "NC_31") (pintype "passive"))
    )
    (net (code "59") (name "unconnected-(IC300-NC-Pad32)") (class "Default")
      (node (ref "IC300") (pin "32") (pinfunction "NC_32") (pintype "passive"))
    )
    (net (code "60") (name "unconnected-(IC300-NC-Pad33)") (class "Default")
      (node (ref "IC300") (pin "33") (pinfunction "NC_33") (pintype "passive"))
    )
    (net (code "61") (name "unconnected-(IC300-NC-Pad34)") (class "Default")
      (node (ref "IC300") (pin "34") (pinfunction "NC_34") (pintype "passive"))
    )
    (net (code "62") (name "unconnected-(IC300-NC-Pad35)") (class "Default")
      (node (ref "IC300") (pin "35") (pinfunction "NC_35") (pintype "passive"))
    )
    (net (code "63") (name "unconnected-(XT300-Pad2)") (class "Default")
      (node (ref "XT300") (pin "2") (pintype "passive"))
    )
    (net (code "64") (name "unconnected-(XT300-Pad4)") (class "Default")
      (node (ref "XT300") (pin "4") (pintype "passive"))
    )
  )
)
